# fonte.net
KiCad netlist of a schematic drawn in EAGLE
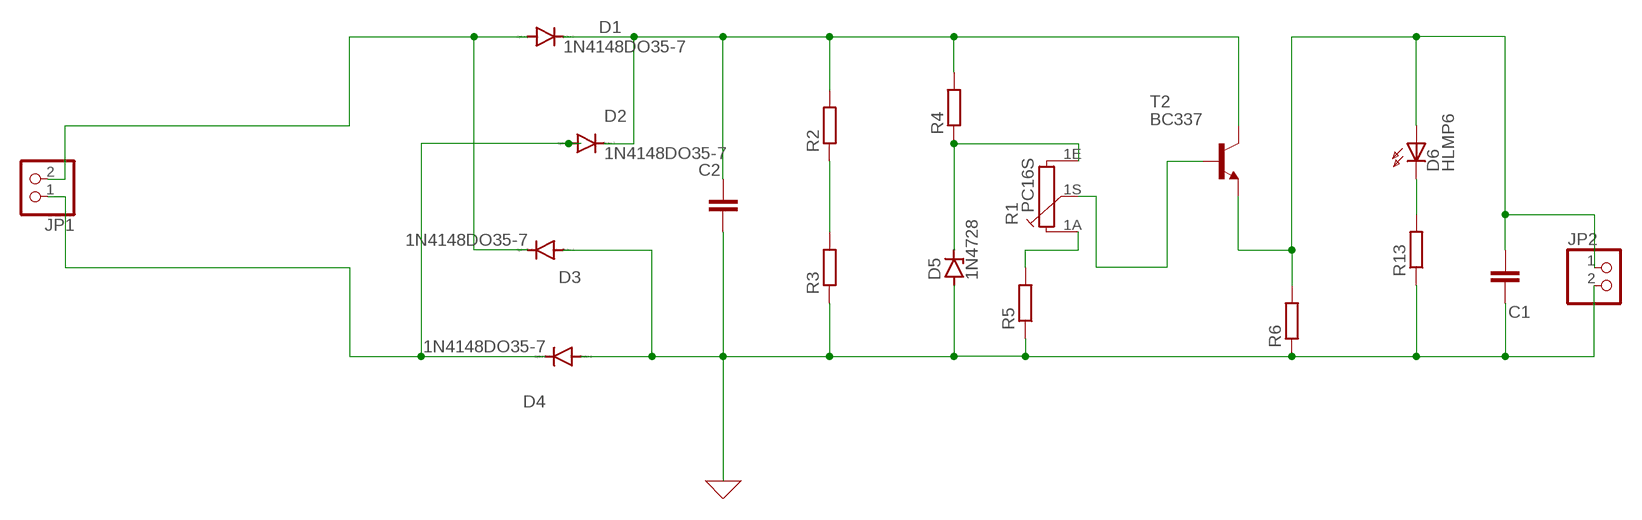
[diagram p0: schematic, sheet 1]

(export (version "E")
  (design (tool "Eeschema 10.0.6"))
  (components
    (comp (ref "C1")
      (value "C5/3")
      (footprint "eagle-import:C5B3")
      (libsource (lib "eagle-import") (part "C5/3"))
    )
    (comp (ref "C2")
      (value "C5/3")
      (footprint "eagle-import:C5B3")
      (libsource (lib "eagle-import") (part "C5/3"))
    )
    (comp (ref "D1")
      (value "1N4148DO35-7")
      (footprint "eagle-import:DO35-7")
      (fields (field (name "SPICEMODEL") "DMOD") (field (name "SPICEPREFIX") "D"))
      (libsource (lib "eagle-import") (part "1N4148DO35-7"))
    )
    (comp (ref "D2")
      (value "1N4148DO35-7")
      (footprint "eagle-import:DO35-7")
      (fields (field (name "SPICEMODEL") "DMOD") (field (name "SPICEPREFIX") "D"))
      (libsource (lib "eagle-import") (part "1N4148DO35-7"))
    )
    (comp (ref "D3")
      (value "1N4148DO35-7")
      (footprint "eagle-import:DO35-7")
      (fields (field (name "SPICEMODEL") "DMOD") (field (name "SPICEPREFIX") "D"))
      (libsource (lib "eagle-import") (part "1N4148DO35-7"))
    )
    (comp (ref "D4")
      (value "1N4148DO35-7")
      (footprint "eagle-import:DO35-7")
      (fields (field (name "SPICEMODEL") "DMOD") (field (name "SPICEPREFIX") "D"))
      (libsource (lib "eagle-import") (part "1N4148DO35-7"))
    )
    (comp (ref "D5")
      (value "1N4728")
      (footprint "eagle-import:DO41Z10")
      (fields (field (name "SPICEMODEL") "DMOD") (field (name "SPICEPREFIX") "D"))
      (libsource (lib "eagle-import") (part "1N4728"))
    )
    (comp (ref "D6")
      (value "HLMP6")
      (footprint "eagle-import:HLMP6")
      (fields (field (name "MF") "AGILENT TECHNOLOGIES") (field (name "MPN") "HLMP-6500"))
      (libsource (lib "eagle-import") (part "HLMP6"))
    )
    (comp (ref "JP1")
      (value "PINHD-1X2")
      (footprint "eagle-import:1X02")
      (libsource (lib "eagle-import") (part "PINHD-1X2"))
    )
    (comp (ref "JP2")
      (value "PINHD-1X2")
      (footprint "eagle-import:1X02")
      (libsource (lib "eagle-import") (part "PINHD-1X2"))
    )
    (comp (ref "R1")
      (value "PC16S")
      (footprint "eagle-import:PC16S")
      (libsource (lib "eagle-import") (part "PC16S"))
    )
    (comp (ref "R2")
      (value "R-EU_0204/7")
      (footprint "eagle-import:0204_7")
      (libsource (lib "eagle-import") (part "R-EU_0204/7"))
    )
    (comp (ref "R3")
      (value "R-EU_0204/7")
      (footprint "eagle-import:0204_7")
      (libsource (lib "eagle-import") (part "R-EU_0204/7"))
    )
    (comp (ref "R4")
      (value "R-EU_0204/7")
      (footprint "eagle-import:0204_7")
      (libsource (lib "eagle-import") (part "R-EU_0204/7"))
    )
    (comp (ref "R5")
      (value "R-EU_0204/7")
      (footprint "eagle-import:0204_7")
      (libsource (lib "eagle-import") (part "R-EU_0204/7"))
    )
    (comp (ref "R6")
      (value "R-EU_0204/7")
      (footprint "eagle-import:0204_7")
      (libsource (lib "eagle-import") (part "R-EU_0204/7"))
    )
    (comp (ref "R13")
      (value "R-EU_0204/7")
      (footprint "eagle-import:0204_7")
      (libsource (lib "eagle-import") (part "R-EU_0204/7"))
    )
    (comp (ref "T2")
      (value "BC337")
      (footprint "eagle-import:TO92")
      (libsource (lib "eagle-import") (part "BC337"))
    )
  )
  (nets
    (net (code "1") (name "GND") (class "Default")
      (node (ref "C1") (pin "1") (pinfunction "1_1") (pintype "passive"))
      (node (ref "C2") (pin "2") (pinfunction "2_2") (pintype "passive"))
      (node (ref "D3") (pin "A") (pinfunction "A_A") (pintype "passive"))
      (node (ref "D4") (pin "A") (pinfunction "A_A") (pintype "passive"))
      (node (ref "D5") (pin "A") (pinfunction "A_A") (pintype "passive"))
      (node (ref "JP2") (pin "2") (pinfunction "2_2") (pintype "passive"))
      (node (ref "R13") (pin "1") (pinfunction "1_1") (pintype "passive"))
      (node (ref "R3") (pin "1") (pinfunction "1_1") (pintype "passive"))
      (node (ref "R5") (pin "1") (pinfunction "1_1") (pintype "passive"))
      (node (ref "R6") (pin "1") (pinfunction "1_1") (pintype "passive"))
    )
    (net (code "2") (name "Net-(D1-PadA)") (class "Default")
      (node (ref "D1") (pin "A") (pinfunction "A_A") (pintype "passive"))
      (node (ref "D3") (pin "C") (pinfunction "C_C") (pintype "passive"))
      (node (ref "JP1") (pin "2") (pinfunction "2_2") (pintype "passive"))
    )
    (net (code "3") (name "Net-(D2-PadA)") (class "Default")
      (node (ref "D2") (pin "A") (pinfunction "A_A") (pintype "passive"))
      (node (ref "D4") (pin "C") (pinfunction "C_C") (pintype "passive"))
      (node (ref "JP1") (pin "1") (pinfunction "1_1") (pintype "passive"))
    )
    (net (code "4") (name "Net-(D5-PadC)") (class "Default")
      (node (ref "D5") (pin "C") (pinfunction "C_C") (pintype "passive"))
      (node (ref "R1") (pin "1E") (pinfunction "1E_1E") (pintype "passive"))
      (node (ref "R4") (pin "1") (pinfunction "1_1") (pintype "passive"))
    )
    (net (code "5") (name "Net-(D6-PadK)") (class "Default")
      (node (ref "D6") (pin "K") (pinfunction "K_K") (pintype "passive"))
      (node (ref "R13") (pin "2") (pinfunction "2_2") (pintype "passive"))
    )
    (net (code "6") (name "Net-(R1-Pad1A)") (class "Default")
      (node (ref "R1") (pin "1A") (pinfunction "1A_1A") (pintype "passive"))
      (node (ref "R5") (pin "2") (pinfunction "2_2") (pintype "passive"))
    )
    (net (code "7") (name "Net-(R2-Pad1)") (class "Default")
      (node (ref "R2") (pin "1") (pinfunction "1_1") (pintype "passive"))
      (node (ref "R3") (pin "2") (pinfunction "2_2") (pintype "passive"))
    )
    (net (code "8") (name "Net-(T2-B)") (class "Default")
      (node (ref "R1") (pin "1S") (pinfunction "1S_1S") (pintype "passive"))
      (node (ref "T2") (pin "2") (pinfunction "B_2") (pintype "passive"))
    )
    (net (code "9") (name "Net-(T2-C)") (class "Default")
      (node (ref "C2") (pin "1") (pinfunction "1_1") (pintype "passive"))
      (node (ref "D1") (pin "C") (pinfunction "C_C") (pintype "passive"))
      (node (ref "D2") (pin "C") (pinfunction "C_C") (pintype "passive"))
      (node (ref "R2") (pin "2") (pinfunction "2_2") (pintype "passive"))
      (node (ref "R4") (pin "2") (pinfunction "2_2") (pintype "passive"))
      (node (ref "T2") (pin "3") (pinfunction "C_3") (pintype "passive"))
    )
    (net (code "10") (name "Net-(T2-E)") (class "Default")
      (node (ref "C1") (pin "2") (pinfunction "2_2") (pintype "passive"))
      (node (ref "D6") (pin "A") (pinfunction "A_A") (pintype "passive"))
      (node (ref "JP2") (pin "1") (pinfunction "1_1") (pintype "passive"))
      (node (ref "R6") (pin "2") (pinfunction "2_2") (pintype "passive"))
      (node (ref "T2") (pin "1") (pinfunction "E_1") (pintype "passive"))
    )
  )
)
